# 001_OverViewDevKIT.net
KiCad netlist of a schematic drawn in Altium Designer
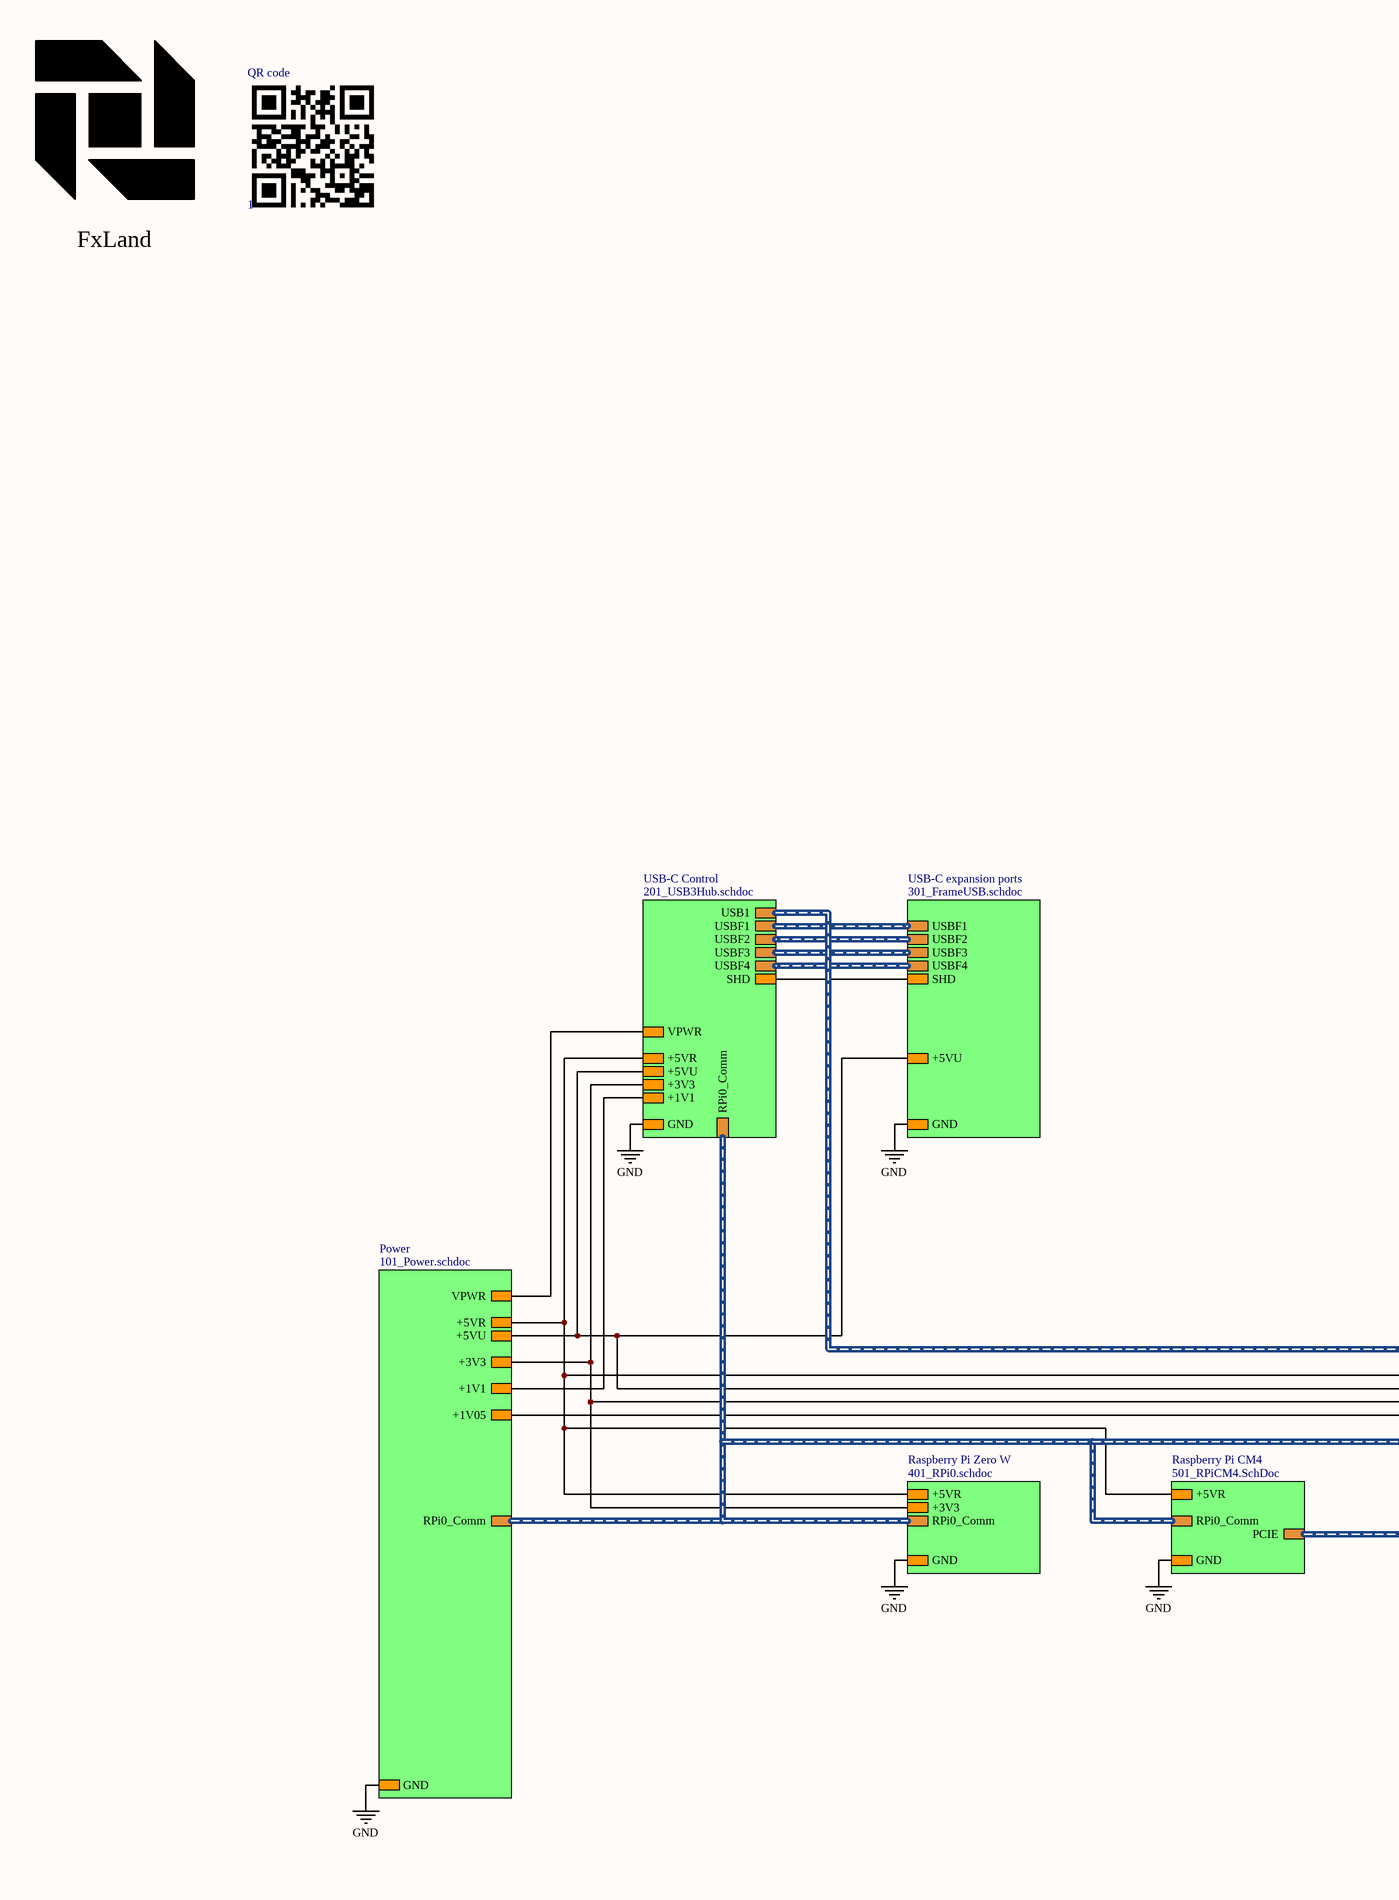
[diagram p0: 001_OverViewDevKIT.SchDoc, left]
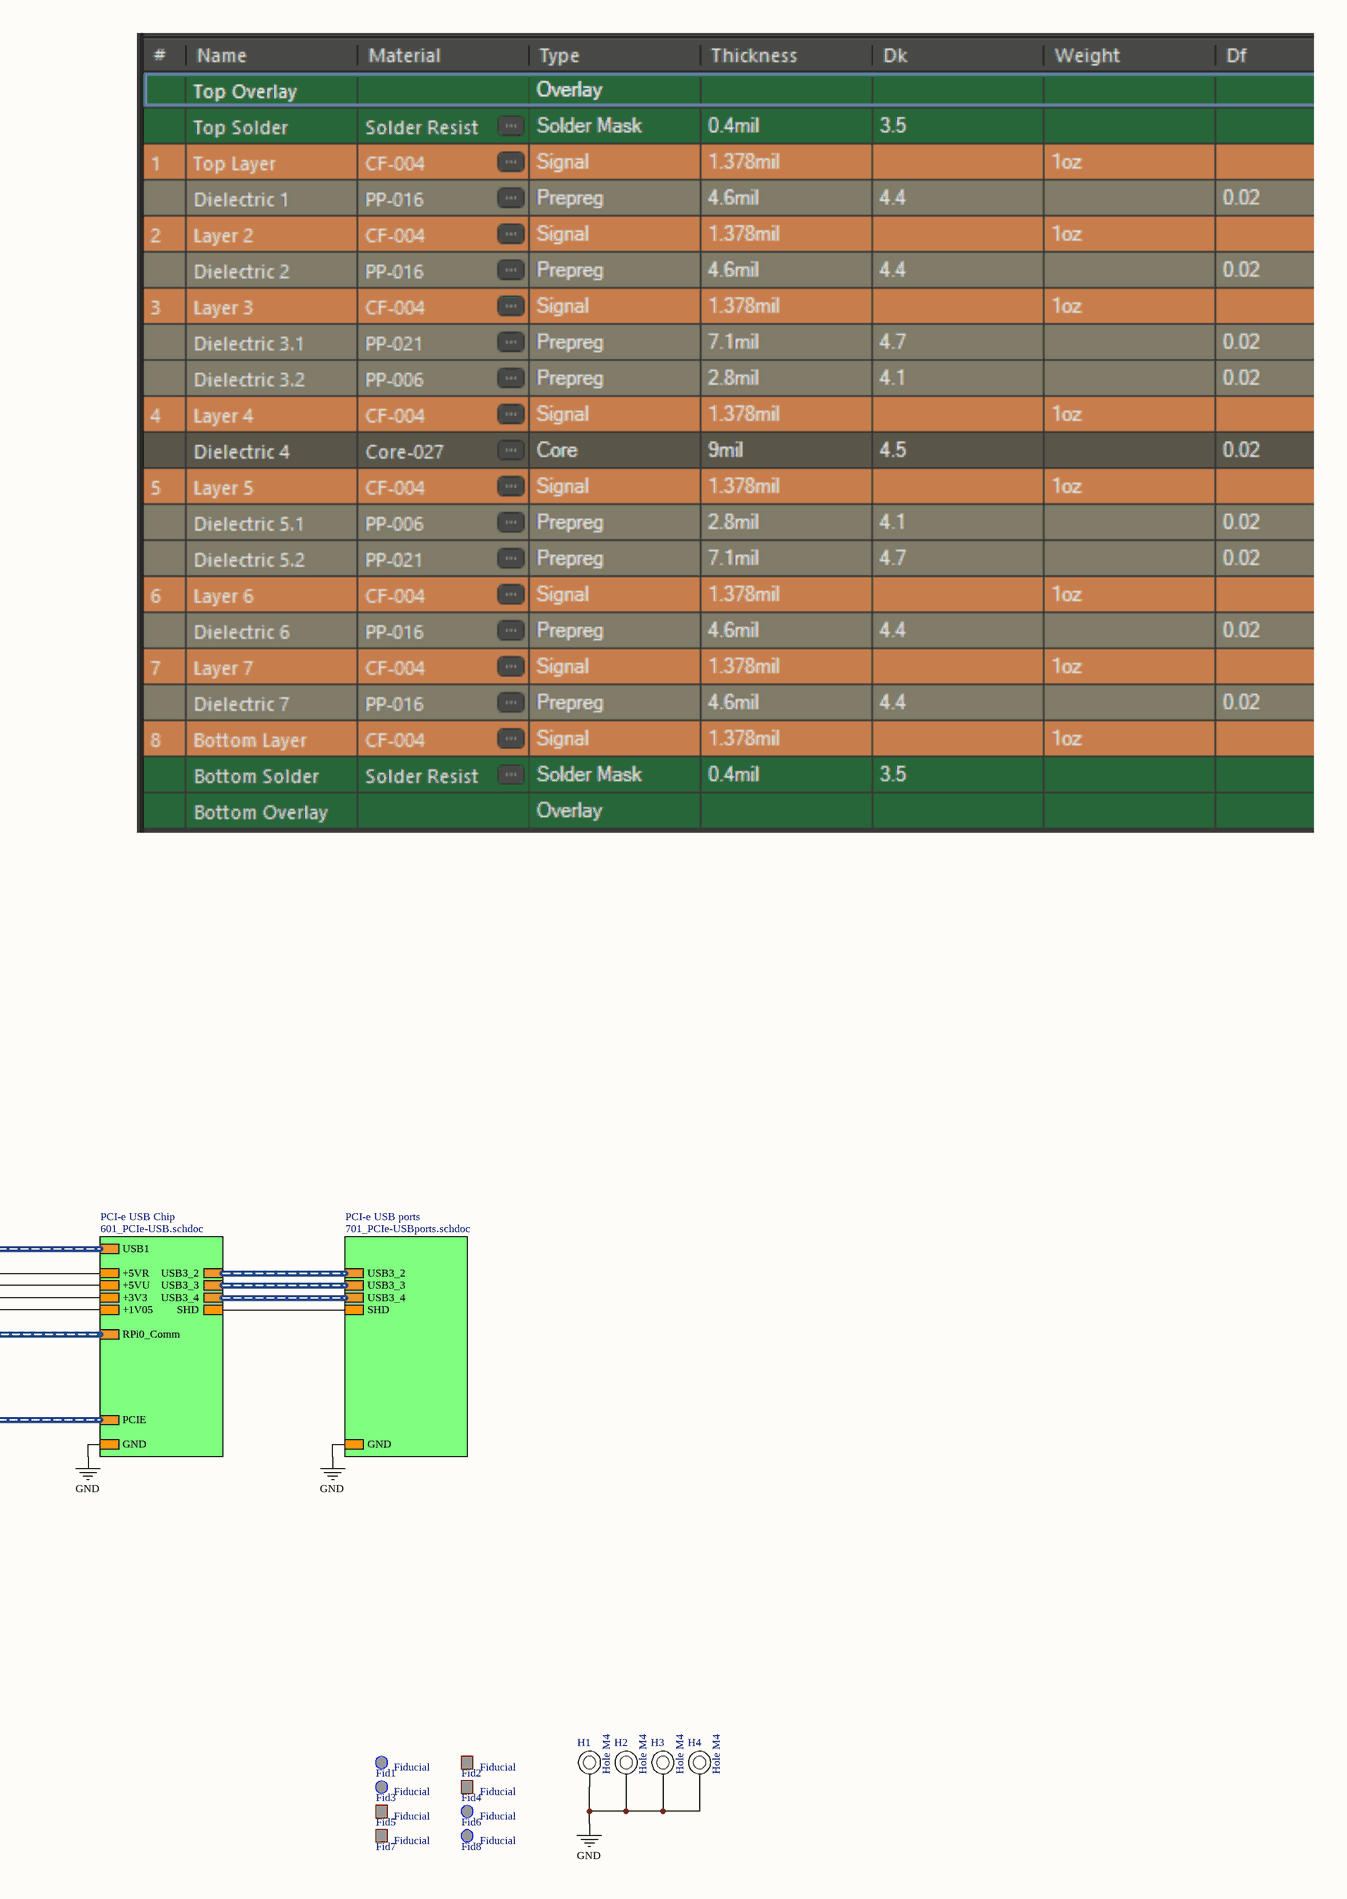
[diagram p1: 001_OverViewDevKIT.SchDoc, right]

(export (version "E")
  (design (tool "Eeschema 10.0.6"))
  (components
    (comp (ref "1")
      (value "QR code")
      (footprint "QR_FXLAND_1")
      (description "QR code FxLand 1")
      (fields (field (name "REFVAL") "QR code") (field (name "PART NUMBER") "ME0023"))
      (libsource (lib "GTS_Database") (part "QR_FXLAND_1"))
    )
    (comp (ref "Fid1")
      (value "Fiducial")
      (footprint "FidR_1.0mm")
      (description "Fiducial Round 1mm")
      (fields (field (name "REFVAL") "Fiducial") (field (name "PART NUMBER") "ME0011"))
      (libsource (lib "GTS_Database") (part "FidR_1.0mm"))
    )
    (comp (ref "Fid2")
      (value "Fiducial")
      (footprint "FidS_1.0mm")
      (description "Fiducial Sqaure 1mm")
      (fields (field (name "REFVAL") "Fiducial") (field (name "PART NUMBER") "ME0012"))
      (libsource (lib "GTS_Database") (part "FidS_1.0mm"))
    )
    (comp (ref "Fid3")
      (value "Fiducial")
      (footprint "FidR_1.0mm")
      (description "Fiducial Round 1mm")
      (fields (field (name "REFVAL") "Fiducial") (field (name "PART NUMBER") "ME0011"))
      (libsource (lib "GTS_Database") (part "FidR_1.0mm"))
    )
    (comp (ref "Fid4")
      (value "Fiducial")
      (footprint "FidS_1.0mm")
      (description "Fiducial Sqaure 1mm")
      (fields (field (name "REFVAL") "Fiducial") (field (name "PART NUMBER") "ME0012"))
      (libsource (lib "GTS_Database") (part "FidS_1.0mm"))
    )
    (comp (ref "Fid5")
      (value "Fiducial")
      (footprint "FidS_1.0mm")
      (description "Fiducial Sqaure 1mm")
      (fields (field (name "REFVAL") "Fiducial") (field (name "PART NUMBER") "ME0012"))
      (libsource (lib "GTS_Database") (part "FidS_1.0mm"))
    )
    (comp (ref "Fid6")
      (value "Fiducial")
      (footprint "FidR_1.0mm")
      (description "Fiducial Round 1mm")
      (fields (field (name "REFVAL") "Fiducial") (field (name "PART NUMBER") "ME0011"))
      (libsource (lib "GTS_Database") (part "FidR_1.0mm"))
    )
    (comp (ref "Fid7")
      (value "Fiducial")
      (footprint "FidS_1.0mm")
      (description "Fiducial Sqaure 1mm")
      (fields (field (name "REFVAL") "Fiducial") (field (name "PART NUMBER") "ME0012"))
      (libsource (lib "GTS_Database") (part "FidS_1.0mm"))
    )
    (comp (ref "Fid8")
      (value "Fiducial")
      (footprint "FidR_1.0mm")
      (description "Fiducial Round 1mm")
      (fields (field (name "REFVAL") "Fiducial") (field (name "PART NUMBER") "ME0011"))
      (libsource (lib "GTS_Database") (part "FidR_1.0mm"))
    )
    (comp (ref "H1")
      (value "Hole M4")
      (footprint "HOLE_M4")
      (description "Mounting Hole M4")
      (fields (field (name "REFVAL") "Hole M4") (field (name "PART NUMBER") "ME0002"))
      (libsource (lib "GTS_Database") (part "HOLE"))
    )
    (comp (ref "H2")
      (value "Hole M4")
      (footprint "HOLE_M4")
      (description "Mounting Hole M4")
      (fields (field (name "REFVAL") "Hole M4") (field (name "PART NUMBER") "ME0002"))
      (libsource (lib "GTS_Database") (part "HOLE"))
    )
    (comp (ref "H3")
      (value "Hole M4")
      (footprint "HOLE_M4")
      (description "Mounting Hole M4")
      (fields (field (name "REFVAL") "Hole M4") (field (name "PART NUMBER") "ME0002"))
      (libsource (lib "GTS_Database") (part "HOLE"))
    )
    (comp (ref "H4")
      (value "Hole M4")
      (footprint "HOLE_M4")
      (description "Mounting Hole M4")
      (fields (field (name "REFVAL") "Hole M4") (field (name "PART NUMBER") "ME0002"))
      (libsource (lib "GTS_Database") (part "HOLE"))
    )
    (comp (ref "Logo FxLand1")
      (value "FxLand")
      (footprint "Logo_FxLand_3")
      (description "Logo FxLand 3")
      (fields (field (name "PART NUMBER") "ME0008"))
      (libsource (lib "GTS_Database") (part "Logo_FxLand_2"))
    )
  )
  (nets
    (net (code "20") (name "GND") (class "Default")
      (node (ref "H1") (pin "1") (pinfunction "1_1") (pintype "passive"))
      (node (ref "H2") (pin "1") (pinfunction "1_1") (pintype "passive"))
      (node (ref "H3") (pin "1") (pinfunction "1_1") (pintype "passive"))
      (node (ref "H4") (pin "1") (pinfunction "1_1") (pintype "passive"))
    )
  )
)
